# bdm.net
KiCad netlist of a schematic drawn in EAGLE
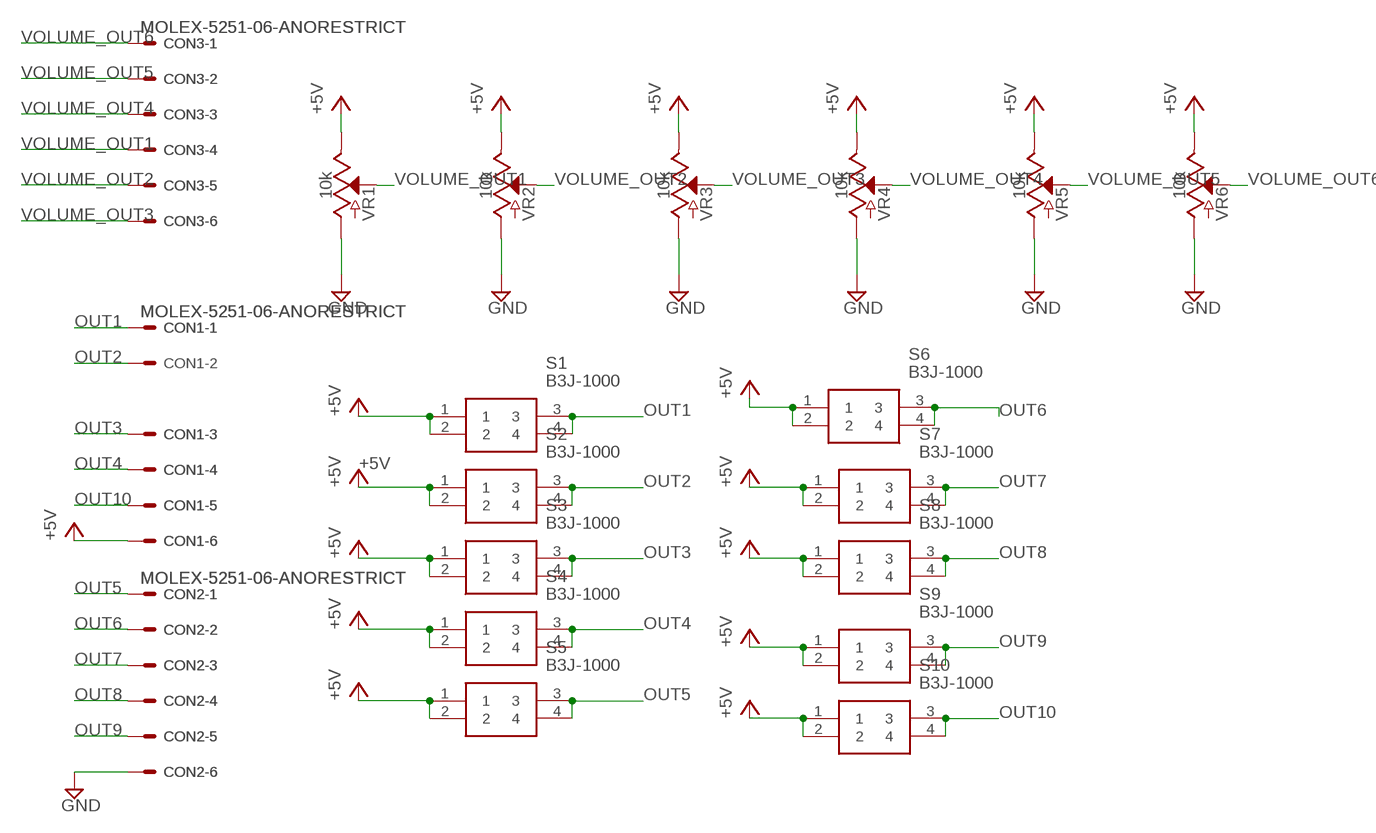
[diagram p0: schematic, sheet 1]

(export (version "E")
  (design (tool "Eeschema 10.0.6"))
  (components
    (comp (ref "CON1")
      (value "MOLEX-5251-06-ANORESTRICT")
      (footprint "eagle-import:5251-06-ANORESTRICT")
      (libsource (lib "eagle-import") (part "MOLEX-5251-06-ANORESTRICT"))
    )
    (comp (ref "CON2")
      (value "MOLEX-5251-06-ANORESTRICT")
      (footprint "eagle-import:5251-06-ANORESTRICT")
      (libsource (lib "eagle-import") (part "MOLEX-5251-06-ANORESTRICT"))
    )
    (comp (ref "CON3")
      (value "MOLEX-5251-06-ANORESTRICT")
      (footprint "eagle-import:5251-06-ANORESTRICT")
      (libsource (lib "eagle-import") (part "MOLEX-5251-06-ANORESTRICT"))
    )
    (comp (ref "S1")
      (value "B3J-1000")
      (footprint "eagle-import:B3J-1_00")
      (fields (field (name "DIGIKEY_PART_NUMBER") "SW819-ND"))
      (libsource (lib "eagle-import") (part "B3J-1000"))
    )
    (comp (ref "S2")
      (value "B3J-1000")
      (footprint "eagle-import:B3J-1_00")
      (fields (field (name "DIGIKEY_PART_NUMBER") "SW819-ND"))
      (libsource (lib "eagle-import") (part "B3J-1000"))
    )
    (comp (ref "S3")
      (value "B3J-1000")
      (footprint "eagle-import:B3J-1_00")
      (fields (field (name "DIGIKEY_PART_NUMBER") "SW819-ND"))
      (libsource (lib "eagle-import") (part "B3J-1000"))
    )
    (comp (ref "S4")
      (value "B3J-1000")
      (footprint "eagle-import:B3J-1_00")
      (fields (field (name "DIGIKEY_PART_NUMBER") "SW819-ND"))
      (libsource (lib "eagle-import") (part "B3J-1000"))
    )
    (comp (ref "S5")
      (value "B3J-1000")
      (footprint "eagle-import:B3J-1_00")
      (fields (field (name "DIGIKEY_PART_NUMBER") "SW819-ND"))
      (libsource (lib "eagle-import") (part "B3J-1000"))
    )
    (comp (ref "S6")
      (value "B3J-1000")
      (footprint "eagle-import:B3J-1_00")
      (fields (field (name "DIGIKEY_PART_NUMBER") "SW819-ND"))
      (libsource (lib "eagle-import") (part "B3J-1000"))
    )
    (comp (ref "S7")
      (value "B3J-1000")
      (footprint "eagle-import:B3J-1_00")
      (fields (field (name "DIGIKEY_PART_NUMBER") "SW819-ND"))
      (libsource (lib "eagle-import") (part "B3J-1000"))
    )
    (comp (ref "S8")
      (value "B3J-1000")
      (footprint "eagle-import:B3J-1_00")
      (fields (field (name "DIGIKEY_PART_NUMBER") "SW819-ND"))
      (libsource (lib "eagle-import") (part "B3J-1000"))
    )
    (comp (ref "S9")
      (value "B3J-1000")
      (footprint "eagle-import:B3J-1_00")
      (fields (field (name "DIGIKEY_PART_NUMBER") "SW819-ND"))
      (libsource (lib "eagle-import") (part "B3J-1000"))
    )
    (comp (ref "S10")
      (value "B3J-1000")
      (footprint "eagle-import:B3J-1_00")
      (fields (field (name "DIGIKEY_PART_NUMBER") "SW819-ND"))
      (libsource (lib "eagle-import") (part "B3J-1000"))
    )
    (comp (ref "VR1")
      (value "10k")
      (footprint "eagle-import:SLIDER-SMALL")
      (libsource (lib "eagle-import") (part "POTENTIOMETER_SLIDE-20MM-1/10W-20%"))
    )
    (comp (ref "VR2")
      (value "10k")
      (footprint "eagle-import:SLIDER-SMALL")
      (libsource (lib "eagle-import") (part "POTENTIOMETER_SLIDE-20MM-1/10W-20%"))
    )
    (comp (ref "VR3")
      (value "10k")
      (footprint "eagle-import:SLIDER-SMALL")
      (libsource (lib "eagle-import") (part "POTENTIOMETER_SLIDE-20MM-1/10W-20%"))
    )
    (comp (ref "VR4")
      (value "10k")
      (footprint "eagle-import:SLIDER-MEDIUM")
      (libsource (lib "eagle-import") (part "POTENTIOMETER_SLIDE-30MM-1/10W-20%"))
    )
    (comp (ref "VR5")
      (value "10k")
      (footprint "eagle-import:SLIDER-MEDIUM")
      (libsource (lib "eagle-import") (part "POTENTIOMETER_SLIDE-30MM-1/10W-20%"))
    )
    (comp (ref "VR6")
      (value "10k")
      (footprint "eagle-import:SLIDER-MEDIUM")
      (libsource (lib "eagle-import") (part "POTENTIOMETER_SLIDE-30MM-1/10W-20%"))
    )
  )
  (nets
    (net (code "1") (name "+5V") (class "Default")
      (node (ref "CON1") (pin "6") (pinfunction "S_6") (pintype "passive"))
      (node (ref "S1") (pin "1") (pinfunction "1_1") (pintype "bidirectional"))
      (node (ref "S1") (pin "2") (pinfunction "2_2") (pintype "bidirectional"))
      (node (ref "S10") (pin "1") (pinfunction "1_1") (pintype "bidirectional"))
      (node (ref "S10") (pin "2") (pinfunction "2_2") (pintype "bidirectional"))
      (node (ref "S2") (pin "1") (pinfunction "1_1") (pintype "bidirectional"))
      (node (ref "S2") (pin "2") (pinfunction "2_2") (pintype "bidirectional"))
      (node (ref "S3") (pin "1") (pinfunction "1_1") (pintype "bidirectional"))
      (node (ref "S3") (pin "2") (pinfunction "2_2") (pintype "bidirectional"))
      (node (ref "S4") (pin "1") (pinfunction "1_1") (pintype "bidirectional"))
      (node (ref "S4") (pin "2") (pinfunction "2_2") (pintype "bidirectional"))
      (node (ref "S5") (pin "1") (pinfunction "1_1") (pintype "bidirectional"))
      (node (ref "S5") (pin "2") (pinfunction "2_2") (pintype "bidirectional"))
      (node (ref "S6") (pin "1") (pinfunction "1_1") (pintype "bidirectional"))
      (node (ref "S6") (pin "2") (pinfunction "2_2") (pintype "bidirectional"))
      (node (ref "S7") (pin "1") (pinfunction "1_1") (pintype "bidirectional"))
      (node (ref "S7") (pin "2") (pinfunction "2_2") (pintype "bidirectional"))
      (node (ref "S8") (pin "1") (pinfunction "1_1") (pintype "bidirectional"))
      (node (ref "S8") (pin "2") (pinfunction "2_2") (pintype "bidirectional"))
      (node (ref "S9") (pin "1") (pinfunction "1_1") (pintype "bidirectional"))
      (node (ref "S9") (pin "2") (pinfunction "2_2") (pintype "bidirectional"))
      (node (ref "VR1") (pin "TOP") (pinfunction "E_TOP") (pintype "passive"))
      (node (ref "VR2") (pin "TOP") (pinfunction "E_TOP") (pintype "passive"))
      (node (ref "VR3") (pin "TOP") (pinfunction "E_TOP") (pintype "passive"))
      (node (ref "VR4") (pin "TOP") (pinfunction "E_TOP") (pintype "passive"))
      (node (ref "VR5") (pin "TOP") (pinfunction "E_TOP") (pintype "passive"))
      (node (ref "VR6") (pin "TOP") (pinfunction "E_TOP") (pintype "passive"))
    )
    (net (code "2") (name "/OUT1") (class "Default")
      (node (ref "CON1") (pin "1") (pinfunction "S_1") (pintype "passive"))
      (node (ref "S1") (pin "3") (pinfunction "3_3") (pintype "bidirectional"))
      (node (ref "S1") (pin "4") (pinfunction "4_4") (pintype "bidirectional"))
    )
    (net (code "3") (name "/OUT2") (class "Default")
      (node (ref "CON1") (pin "2") (pinfunction "S_2") (pintype "passive"))
      (node (ref "S2") (pin "3") (pinfunction "3_3") (pintype "bidirectional"))
      (node (ref "S2") (pin "4") (pinfunction "4_4") (pintype "bidirectional"))
    )
    (net (code "4") (name "/OUT3") (class "Default")
      (node (ref "CON1") (pin "3") (pinfunction "S_3") (pintype "passive"))
      (node (ref "S3") (pin "3") (pinfunction "3_3") (pintype "bidirectional"))
      (node (ref "S3") (pin "4") (pinfunction "4_4") (pintype "bidirectional"))
    )
    (net (code "5") (name "/OUT4") (class "Default")
      (node (ref "CON1") (pin "4") (pinfunction "S_4") (pintype "passive"))
      (node (ref "S4") (pin "3") (pinfunction "3_3") (pintype "bidirectional"))
      (node (ref "S4") (pin "4") (pinfunction "4_4") (pintype "bidirectional"))
    )
    (net (code "6") (name "/OUT5") (class "Default")
      (node (ref "CON2") (pin "1") (pinfunction "S_1") (pintype "passive"))
      (node (ref "S5") (pin "3") (pinfunction "3_3") (pintype "bidirectional"))
      (node (ref "S5") (pin "4") (pinfunction "4_4") (pintype "bidirectional"))
    )
    (net (code "7") (name "/OUT6") (class "Default")
      (node (ref "CON2") (pin "2") (pinfunction "S_2") (pintype "passive"))
      (node (ref "S6") (pin "3") (pinfunction "3_3") (pintype "bidirectional"))
      (node (ref "S6") (pin "4") (pinfunction "4_4") (pintype "bidirectional"))
    )
    (net (code "8") (name "/OUT7") (class "Default")
      (node (ref "CON2") (pin "3") (pinfunction "S_3") (pintype "passive"))
      (node (ref "S7") (pin "3") (pinfunction "3_3") (pintype "bidirectional"))
      (node (ref "S7") (pin "4") (pinfunction "4_4") (pintype "bidirectional"))
    )
    (net (code "9") (name "/OUT8") (class "Default")
      (node (ref "CON2") (pin "4") (pinfunction "S_4") (pintype "passive"))
      (node (ref "S8") (pin "3") (pinfunction "3_3") (pintype "bidirectional"))
      (node (ref "S8") (pin "4") (pinfunction "4_4") (pintype "bidirectional"))
    )
    (net (code "10") (name "/OUT9") (class "Default")
      (node (ref "CON2") (pin "5") (pinfunction "S_5") (pintype "passive"))
      (node (ref "S9") (pin "3") (pinfunction "3_3") (pintype "bidirectional"))
      (node (ref "S9") (pin "4") (pinfunction "4_4") (pintype "bidirectional"))
    )
    (net (code "11") (name "/OUT10") (class "Default")
      (node (ref "CON1") (pin "5") (pinfunction "S_5") (pintype "passive"))
      (node (ref "S10") (pin "3") (pinfunction "3_3") (pintype "bidirectional"))
      (node (ref "S10") (pin "4") (pinfunction "4_4") (pintype "bidirectional"))
    )
    (net (code "12") (name "/VOLUME_OUT1") (class "Default")
      (node (ref "CON3") (pin "4") (pinfunction "S_4") (pintype "passive"))
      (node (ref "VR1") (pin "WIPER") (pinfunction "S_WIPER") (pintype "passive"))
    )
    (net (code "13") (name "/VOLUME_OUT2") (class "Default")
      (node (ref "CON3") (pin "5") (pinfunction "S_5") (pintype "passive"))
      (node (ref "VR2") (pin "WIPER") (pinfunction "S_WIPER") (pintype "passive"))
    )
    (net (code "14") (name "/VOLUME_OUT3") (class "Default")
      (node (ref "CON3") (pin "6") (pinfunction "S_6") (pintype "passive"))
      (node (ref "VR3") (pin "WIPER") (pinfunction "S_WIPER") (pintype "passive"))
    )
    (net (code "15") (name "/VOLUME_OUT4") (class "Default")
      (node (ref "CON3") (pin "3") (pinfunction "S_3") (pintype "passive"))
      (node (ref "VR4") (pin "WIPER") (pinfunction "S_WIPER") (pintype "passive"))
    )
    (net (code "16") (name "/VOLUME_OUT5") (class "Default")
      (node (ref "CON3") (pin "2") (pinfunction "S_2") (pintype "passive"))
      (node (ref "VR5") (pin "WIPER") (pinfunction "S_WIPER") (pintype "passive"))
    )
    (net (code "17") (name "/VOLUME_OUT6") (class "Default")
      (node (ref "CON3") (pin "1") (pinfunction "S_1") (pintype "passive"))
      (node (ref "VR6") (pin "WIPER") (pinfunction "S_WIPER") (pintype "passive"))
    )
    (net (code "18") (name "GND") (class "Default")
      (node (ref "CON2") (pin "6") (pinfunction "S_6") (pintype "passive"))
      (node (ref "VR1") (pin "BOTTOM") (pinfunction "A_BOTTOM") (pintype "passive"))
      (node (ref "VR2") (pin "BOTTOM") (pinfunction "A_BOTTOM") (pintype "passive"))
      (node (ref "VR3") (pin "BOTTOM") (pinfunction "A_BOTTOM") (pintype "passive"))
      (node (ref "VR4") (pin "BOTTOM") (pinfunction "A_BOTTOM") (pintype "passive"))
      (node (ref "VR5") (pin "BOTTOM") (pinfunction "A_BOTTOM") (pintype "passive"))
      (node (ref "VR6") (pin "BOTTOM") (pinfunction "A_BOTTOM") (pintype "passive"))
    )
  )
)
